# MAIN.net
KiCad netlist of a schematic drawn in Altium Designer
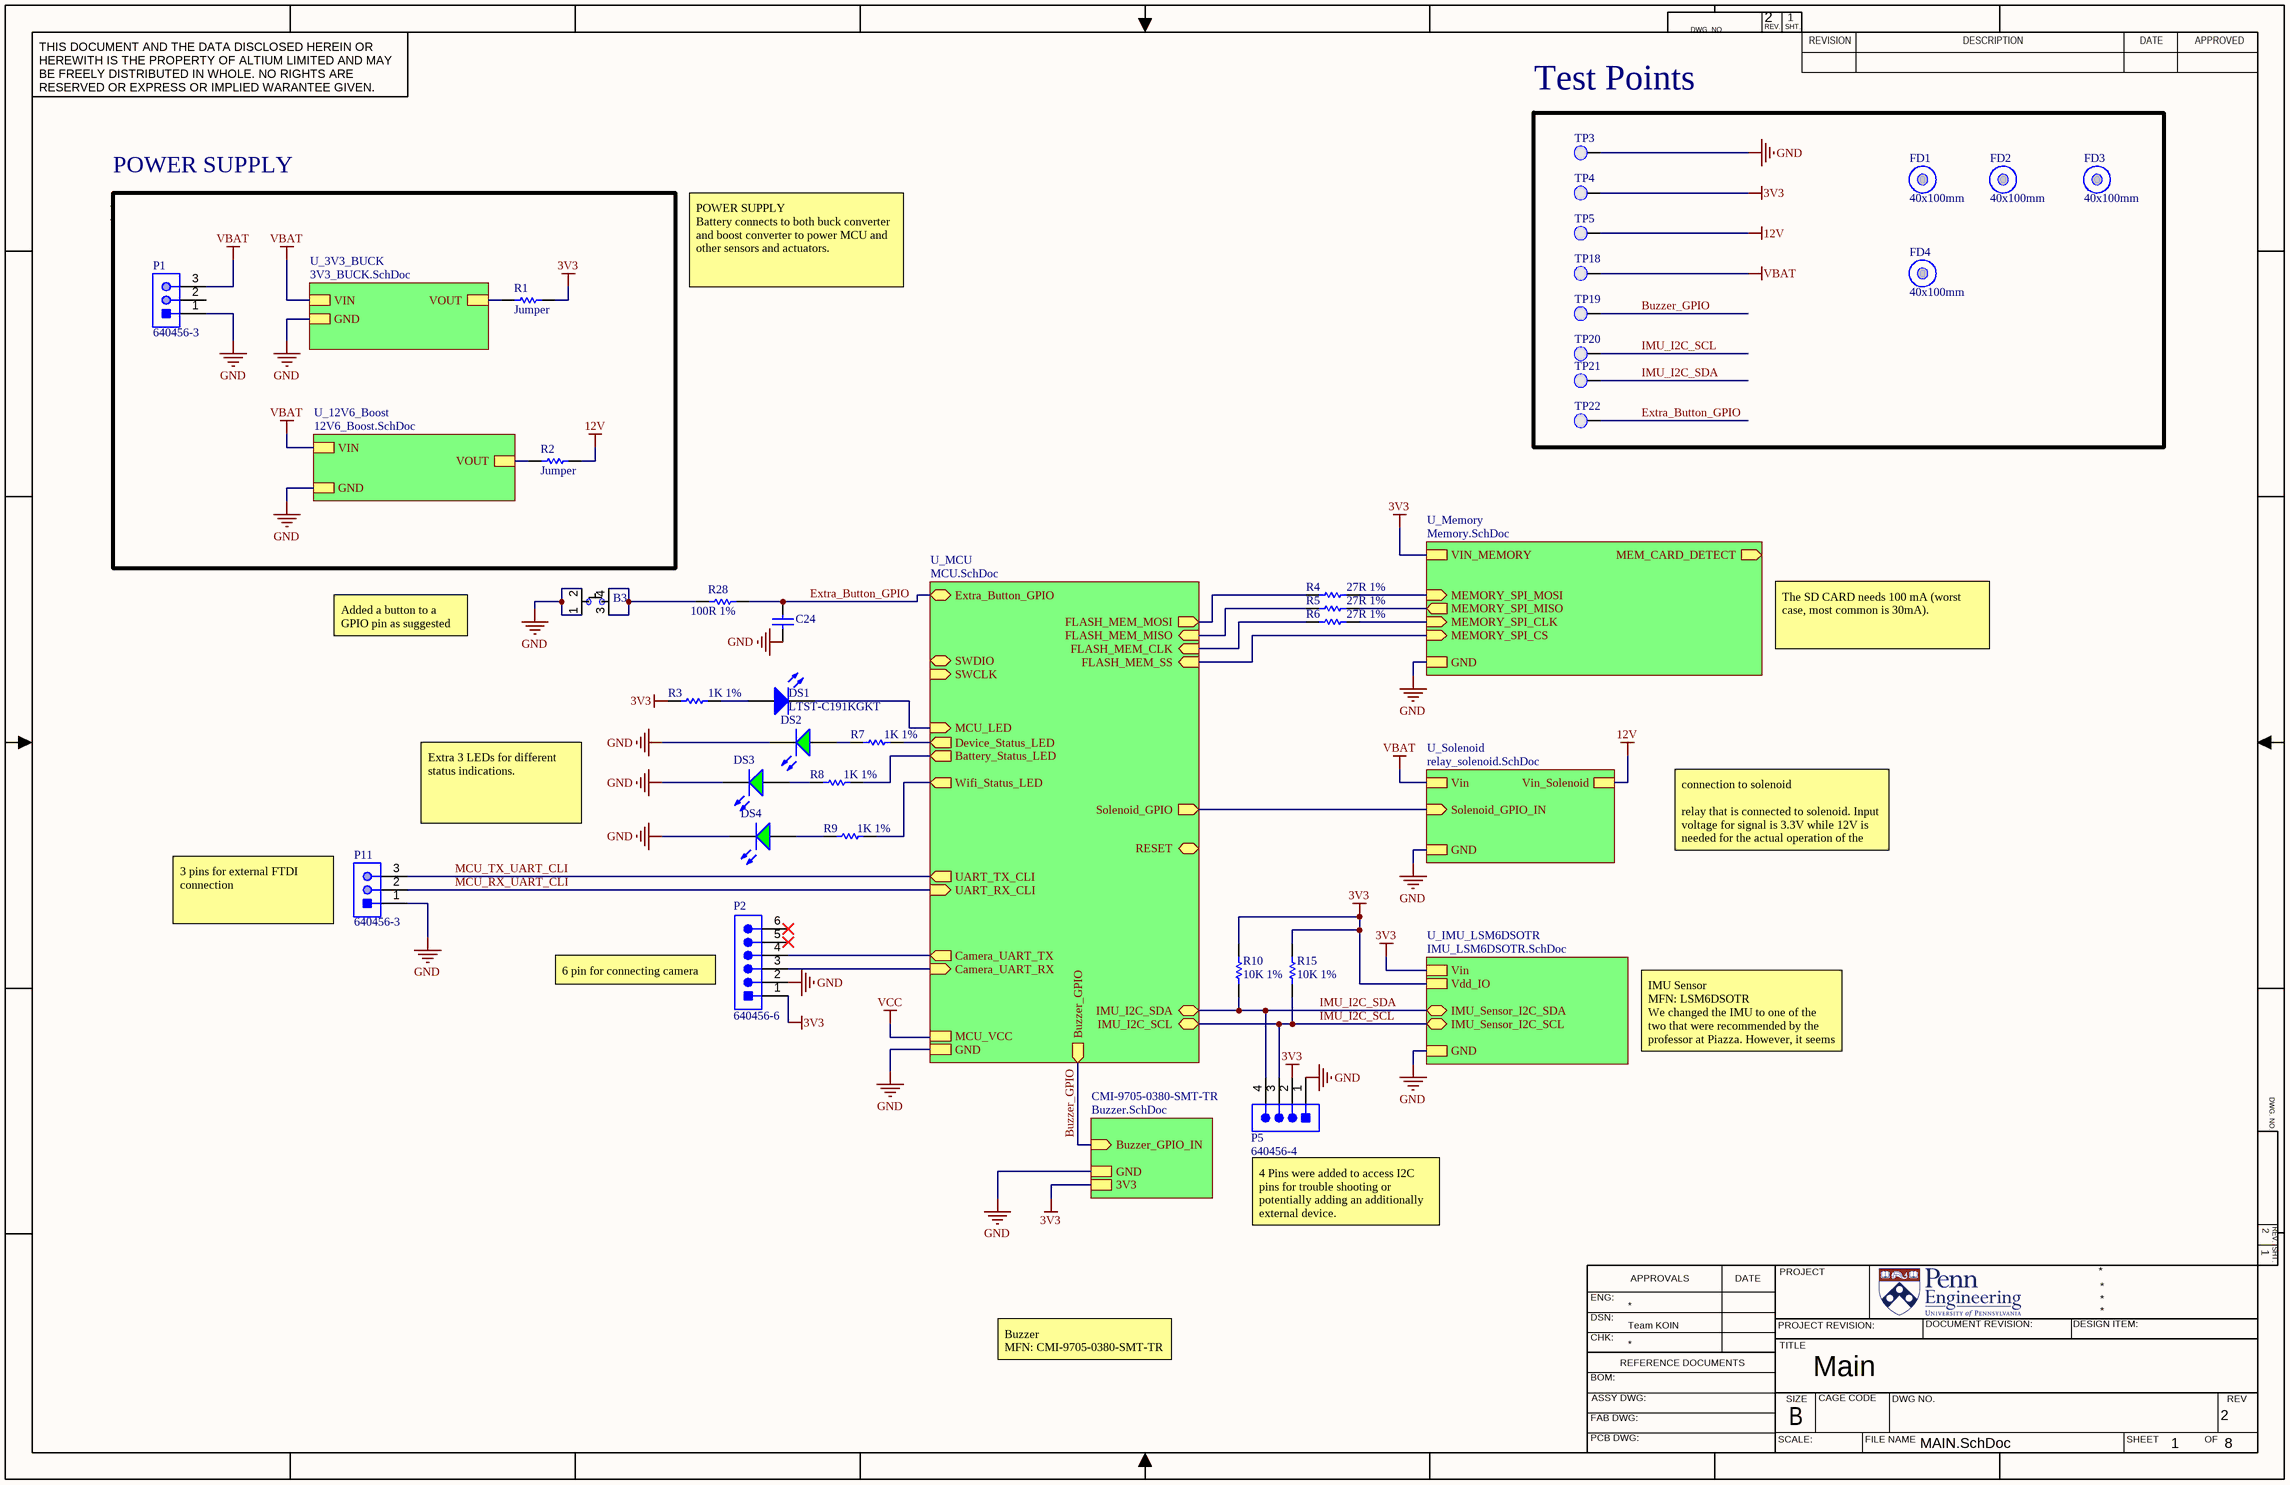
[diagram p0: MAIN.SchDoc]

(export (version "E")
  (design (tool "Eeschema 10.0.6"))
  (components
    (comp (ref "B3")
      (value "PTS810 SJK 250 SMTR LFS")
      (footprint "PTS810 SJK 250 SMTR LFS")
      (description "SWITCH TACTILE SPST-NO 0.05A 16V Tactile Switch SPST-NO Top Actuated Surface Mount")
      (fields
        (field (name "MANUFACTURER") "ITT /  C&K Components")
        (field (name "MANUFACTURER PART NUMBER") "PTS810SJK250SMTRLFS")
      )
      (libsource (lib "Schematics") (part "PTS810 SJK 250 SMTR LFS"))
    )
    (comp (ref "C24")
      (value "CAP 1uF 16V 0603(1608)")
      (footprint "CAPC0603(1608)100_N")
      (description "CAP 1uF 16V ±5% 0603 (1608 Metric) Thickness 1mm SMD")
      (fields (field (name "TOLERANCE") "Â±5%"))
      (libsource (lib "Altium Content Vault") (part "CAP"))
    )
    (comp (ref "DS1")
      (value "LTST-C191KGKT")
      (footprint "LITE-ON-LTST-C191KRKT-2_V")
      (description "Chip LED, Green, 574 nm, 40 pF, -55 to 85 degC, 2-Pin SMD, RoHS, Tape and Reel")
      (fields (field (name "MANUFACTURER") "Lite-On"))
      (libsource (lib "Altium Content Vault") (part "LED-AK-2"))
    )
    (comp (ref "DS2")
      (value "~")
      (footprint "LTST-C170GKT_V")
      (description "LED Uni-Color Green, 100 mW, 120 mA, -55 to 85 degC, 2-Pin SMD, RoHS, Tape and Reel")
      (fields (field (name "MANUFACTURER") "Lite-On"))
      (libsource (lib "Altium Content Vault") (part "LED-GREEN-AK-2"))
    )
    (comp (ref "DS3")
      (value "~")
      (footprint "LTST-C170GKT_V")
      (description "LED Uni-Color Green, 100 mW, 120 mA, -55 to 85 degC, 2-Pin SMD, RoHS, Tape and Reel")
      (fields (field (name "MANUFACTURER") "Lite-On"))
      (libsource (lib "Altium Content Vault") (part "LED-GREEN-AK-2"))
    )
    (comp (ref "DS4")
      (value "~")
      (footprint "LTST-C170GKT_V")
      (description "LED Uni-Color Green, 100 mW, 120 mA, -55 to 85 degC, 2-Pin SMD, RoHS, Tape and Reel")
      (fields (field (name "MANUFACTURER") "Lite-On"))
      (libsource (lib "Altium Content Vault") (part "LED-GREEN-AK-2"))
    )
    (comp (ref "FD1")
      (value "40x100mm")
      (footprint "Fiducial_FT")
      (description "Fiducial 40x100mm")
      (libsource (lib "Components - 01.02.21 - 21.11") (part "CMP-00174-A.4"))
    )
    (comp (ref "FD2")
      (value "40x100mm")
      (footprint "Fiducial_FT")
      (description "Fiducial 40x100mm")
      (libsource (lib "Components - 01.02.21 - 21.11") (part "CMP-00174-A.4"))
    )
    (comp (ref "FD3")
      (value "40x100mm")
      (footprint "Fiducial_FT")
      (description "Fiducial 40x100mm")
      (libsource (lib "Components - 01.02.21 - 21.11") (part "CMP-00174-A.4"))
    )
    (comp (ref "FD4")
      (value "40x100mm")
      (footprint "Fiducial_FT")
      (description "Fiducial 40x100mm")
      (libsource (lib "Components - 01.02.21 - 21.11") (part "CMP-00174-A.4"))
    )
    (comp (ref "P1")
      (value "640456-3")
      (footprint "TECO-640456-3")
      (description "Male Header, Pitch 2.54 mm, 1 x 3 Position, Height 10.03 mm, Tail Length 3.56 mm, -55 to 105 degC")
      (fields (field (name "MANUFACTURER") "TE Connectivity"))
      (libsource (lib "Altium Content Vault") (part "CN-1P-M-R3"))
    )
    (comp (ref "P2")
      (value "640456-6")
      (footprint "TECO-640456-6_V")
      (fields (field (name "MANUFACTURER") "TE Connectivity"))
      (libsource (lib "Altium Content Vault") (part "CN-1P-M-R6"))
    )
    (comp (ref "P5")
      (value "640456-4")
      (footprint "TECO-640456-4")
      (description "Male Header, Pitch 2.54 mm, 1 x 4 Position, Height 10.03 mm, Tail Length 3.56 mm, RoHS, Bulk")
      (fields (field (name "MANUFACTURER") "TE Connectivity"))
      (libsource (lib "Altium Content Vault") (part "CN-1P-M-R4"))
    )
    (comp (ref "P11")
      (value "640456-3")
      (footprint "TECO-640456-3")
      (description "Male Header, Pitch 2.54 mm, 1 x 3 Position, Height 10.03 mm, Tail Length 3.56 mm, -55 to 105 degC")
      (fields (field (name "MANUFACTURER") "TE Connectivity"))
      (libsource (lib "Altium Content Vault") (part "CN-1P-M-R3"))
    )
    (comp (ref "R1")
      (value "Jumper")
      (footprint "RESC0805(2012)_N")
      (description "Jumper 0805 (2012 Metric)")
      (fields (field (name "TOLERANCE") "None"))
      (libsource (lib "Altium Content Vault") (part "RES"))
    )
    (comp (ref "R2")
      (value "Jumper")
      (footprint "RESC0805(2012)_N")
      (description "Jumper 0805 (2012 Metric)")
      (fields (field (name "TOLERANCE") "None"))
      (libsource (lib "Altium Content Vault") (part "RES"))
    )
    (comp (ref "R3")
      (value "1K 1%")
      (footprint "RESC0603(1608)_N")
      (description "1K 0.1W 1% 0603 (1608 Metric)  SMD")
      (fields (field (name "TOLERANCE") "1 %") (field (name "POWER") "0.1 W"))
      (libsource (lib "Altium Content Vault") (part "RES"))
    )
    (comp (ref "R4")
      (value "27R 1%")
      (footprint "RESC0603(1608)_N")
      (description "27R 0.1W 1% 0603 (1608 Metric)  SMD")
      (fields (field (name "TOLERANCE") "1 %") (field (name "POWER") "0.1 W"))
      (libsource (lib "Altium Content Vault") (part "RES"))
    )
    (comp (ref "R5")
      (value "27R 1%")
      (footprint "RESC0603(1608)_N")
      (description "27R 0.1W 1% 0603 (1608 Metric)  SMD")
      (fields (field (name "TOLERANCE") "1 %") (field (name "POWER") "0.1 W"))
      (libsource (lib "Altium Content Vault") (part "RES"))
    )
    (comp (ref "R6")
      (value "27R 1%")
      (footprint "RESC0603(1608)_N")
      (description "27R 0.1W 1% 0603 (1608 Metric)  SMD")
      (fields (field (name "TOLERANCE") "1 %") (field (name "POWER") "0.1 W"))
      (libsource (lib "Altium Content Vault") (part "RES"))
    )
    (comp (ref "R7")
      (value "1K 1%")
      (footprint "RESC0603(1608)_M")
      (description "1K 0.1W 1% 0603 (1608 Metric)  SMD")
      (fields (field (name "TOLERANCE") "1 %") (field (name "POWER") "0.1 W"))
      (libsource (lib "Altium Content Vault") (part "RES"))
    )
    (comp (ref "R8")
      (value "1K 1%")
      (footprint "RESC0603(1608)_M")
      (description "1K 0.1W 1% 0603 (1608 Metric)  SMD")
      (fields (field (name "TOLERANCE") "1 %") (field (name "POWER") "0.1 W"))
      (libsource (lib "Altium Content Vault") (part "RES"))
    )
    (comp (ref "R9")
      (value "1K 1%")
      (footprint "RESC0603(1608)_M")
      (description "1K 0.1W 1% 0603 (1608 Metric)  SMD")
      (fields (field (name "TOLERANCE") "1 %") (field (name "POWER") "0.1 W"))
      (libsource (lib "Altium Content Vault") (part "RES"))
    )
    (comp (ref "R10")
      (value "10K 1%")
      (footprint "RESC0603(1608)_N")
      (description "10K 0.1W 1% 0603 (1608 Metric)  SMD")
      (fields (field (name "POWER") "0.1 W") (field (name "TOLERANCE") "1 %"))
      (libsource (lib "Altium Content Vault") (part "RES"))
    )
    (comp (ref "R15")
      (value "10K 1%")
      (footprint "RESC0603(1608)_N")
      (description "10K 0.1W 1% 0603 (1608 Metric)  SMD")
      (fields (field (name "POWER") "0.1 W") (field (name "TOLERANCE") "1 %"))
      (libsource (lib "Altium Content Vault") (part "RES"))
    )
    (comp (ref "R28")
      (value "100R 1%")
      (footprint "RESC0603(1608)_N")
      (description "100R 0.1W 1% 0603 (1608 Metric)  SMD")
      (fields (field (name "TOLERANCE") "1 %") (field (name "POWER") "0.1 W"))
      (libsource (lib "Altium Content Vault") (part "RES"))
    )
    (comp (ref "TP3")
      (value "0.1\" Pad")
      (footprint "PCBComponent")
      (libsource (lib "Components - 12.02.20 - 18.05") (part "0.1{dblquote} Pad-A.4"))
    )
    (comp (ref "TP4")
      (value "0.1\" Pad")
      (footprint "PCBComponent")
      (libsource (lib "Components - 12.02.20 - 18.05") (part "0.1{dblquote} Pad-A.4"))
    )
    (comp (ref "TP5")
      (value "0.1\" Pad")
      (footprint "PCBComponent")
      (libsource (lib "Components - 12.02.20 - 18.05") (part "0.1{dblquote} Pad-A.4"))
    )
    (comp (ref "TP18")
      (value "0.1\" Pad")
      (footprint "PCBComponent")
      (libsource (lib "Components - 12.02.20 - 18.05") (part "0.1{dblquote} Pad-A.4"))
    )
    (comp (ref "TP19")
      (value "0.1\" Pad")
      (footprint "PCBComponent")
      (libsource (lib "Components - 12.02.20 - 18.05") (part "0.1{dblquote} Pad-A.4"))
    )
    (comp (ref "TP20")
      (value "0.1\" Pad")
      (footprint "PCBComponent")
      (libsource (lib "Components - 12.02.20 - 18.05") (part "0.1{dblquote} Pad-A.4"))
    )
    (comp (ref "TP21")
      (value "0.1\" Pad")
      (footprint "PCBComponent")
      (libsource (lib "Components - 12.02.20 - 18.05") (part "0.1{dblquote} Pad-A.4"))
    )
    (comp (ref "TP22")
      (value "0.1\" Pad")
      (footprint "PCBComponent")
      (libsource (lib "Components - 12.02.20 - 18.05") (part "0.1{dblquote} Pad-A.4"))
    )
  )
  (nets
    (net (code "1") (name "/Battery_Status_LED") (class "Default")
      (node (ref "R8") (pin "1") (pinfunction "1_1") (pintype "passive"))
    )
    (net (code "2") (name "/Buzzer_GPIO") (class "Default")
      (node (ref "TP19") (pin "1") (pinfunction "PAD_1") (pintype "passive"))
    )
    (net (code "3") (name "/Camera_UART_RX") (class "Default")
      (node (ref "P2") (pin "3") (pinfunction "3_3") (pintype "passive"))
    )
    (net (code "4") (name "/Camera_UART_TX") (class "Default")
      (node (ref "P2") (pin "4") (pinfunction "4_4") (pintype "passive"))
    )
    (net (code "5") (name "/Device_Status_LED") (class "Default")
      (node (ref "R7") (pin "1") (pinfunction "1_1") (pintype "passive"))
    )
    (net (code "6") (name "/Extra_Button_GPIO") (class "Default")
      (node (ref "C24") (pin "2") (pinfunction "2_2") (pintype "passive"))
      (node (ref "R28") (pin "2") (pinfunction "2_2") (pintype "passive"))
      (node (ref "TP22") (pin "1") (pinfunction "PAD_1") (pintype "passive"))
    )
    (net (code "7") (name "/FLASH_MEM_CLK") (class "Default")
      (node (ref "R6") (pin "1") (pinfunction "1_1") (pintype "passive"))
    )
    (net (code "8") (name "/FLASH_MEM_MISO") (class "Default")
      (node (ref "R5") (pin "1") (pinfunction "1_1") (pintype "passive"))
    )
    (net (code "9") (name "/FLASH_MEM_MOSI") (class "Default")
      (node (ref "R4") (pin "1") (pinfunction "1_1") (pintype "passive"))
    )
    (net (code "11") (name "/IMU_I2C_SCL") (class "Default")
      (node (ref "P5") (pin "3") (pinfunction "3_3") (pintype "passive"))
      (node (ref "R15") (pin "1") (pinfunction "1_1") (pintype "passive"))
      (node (ref "TP20") (pin "1") (pinfunction "PAD_1") (pintype "passive"))
    )
    (net (code "12") (name "/IMU_I2C_SDA") (class "Default")
      (node (ref "P5") (pin "4") (pinfunction "4_4") (pintype "passive"))
      (node (ref "R10") (pin "1") (pinfunction "1_1") (pintype "passive"))
      (node (ref "TP21") (pin "1") (pinfunction "PAD_1") (pintype "passive"))
    )
    (net (code "13") (name "/MCU_LED") (class "Default")
      (node (ref "DS1") (pin "2") (pinfunction "K_2") (pintype "passive"))
    )
    (net (code "14") (name "/MCU_RX_UART_CLI") (class "Default")
      (node (ref "P11") (pin "2") (pinfunction "2_2") (pintype "passive"))
    )
    (net (code "15") (name "/MCU_TX_UART_CLI") (class "Default")
      (node (ref "P11") (pin "3") (pinfunction "3_3") (pintype "passive"))
    )
    (net (code "17") (name "/MEMORY_SPI_CLK") (class "Default")
      (node (ref "R6") (pin "2") (pinfunction "2_2") (pintype "passive"))
    )
    (net (code "18") (name "/MEMORY_SPI_MISO") (class "Default")
      (node (ref "R5") (pin "2") (pinfunction "2_2") (pintype "passive"))
    )
    (net (code "19") (name "/MEMORY_SPI_MOSI") (class "Default")
      (node (ref "R4") (pin "2") (pinfunction "2_2") (pintype "passive"))
    )
    (net (code "25") (name "/VOUT") (class "Default")
      (node (ref "R2") (pin "1") (pinfunction "1_1") (pintype "passive"))
    )
    (net (code "26") (name "/VOUT_1") (class "Default")
      (node (ref "R1") (pin "1") (pinfunction "1_1") (pintype "passive"))
    )
    (net (code "27") (name "/Wifi_Status_LED") (class "Default")
      (node (ref "R9") (pin "2") (pinfunction "2_2") (pintype "passive"))
    )
    (net (code "28") (name "3V3") (class "Default")
      (node (ref "P2") (pin "1") (pinfunction "1_1") (pintype "passive"))
      (node (ref "P5") (pin "2") (pinfunction "2_2") (pintype "passive"))
      (node (ref "R1") (pin "2") (pinfunction "2_2") (pintype "passive"))
      (node (ref "R10") (pin "2") (pinfunction "2_2") (pintype "passive"))
      (node (ref "R15") (pin "2") (pinfunction "2_2") (pintype "passive"))
      (node (ref "R3") (pin "1") (pinfunction "1_1") (pintype "passive"))
      (node (ref "TP4") (pin "1") (pinfunction "PAD_1") (pintype "passive"))
    )
    (net (code "29") (name "12V") (class "Default")
      (node (ref "R2") (pin "2") (pinfunction "2_2") (pintype "passive"))
      (node (ref "TP5") (pin "1") (pinfunction "PAD_1") (pintype "passive"))
    )
    (net (code "30") (name "GND") (class "Default")
      (node (ref "B3") (pin "1") (pinfunction "1_1") (pintype "power_in"))
      (node (ref "B3") (pin "2") (pinfunction "2_2") (pintype "power_in"))
      (node (ref "C24") (pin "1") (pinfunction "1_1") (pintype "passive"))
      (node (ref "DS2") (pin "2") (pinfunction "K_2") (pintype "passive"))
      (node (ref "DS3") (pin "2") (pinfunction "K_2") (pintype "passive"))
      (node (ref "DS4") (pin "2") (pinfunction "K_2") (pintype "passive"))
      (node (ref "P1") (pin "1") (pinfunction "1_1") (pintype "passive"))
      (node (ref "P11") (pin "1") (pinfunction "1_1") (pintype "passive"))
      (node (ref "P2") (pin "2") (pinfunction "2_2") (pintype "passive"))
      (node (ref "P5") (pin "1") (pinfunction "1_1") (pintype "passive"))
      (node (ref "TP3") (pin "1") (pinfunction "PAD_1") (pintype "passive"))
    )
    (net (code "31") (name "Net-(B3-Pad3)") (class "Default")
      (node (ref "B3") (pin "3") (pinfunction "3_3") (pintype "power_in"))
      (node (ref "B3") (pin "4") (pinfunction "4_4") (pintype "power_in"))
      (node (ref "R28") (pin "1") (pinfunction "1_1") (pintype "passive"))
    )
    (net (code "32") (name "Net-(DS1-A)") (class "Default")
      (node (ref "DS1") (pin "1") (pinfunction "A_1") (pintype "passive"))
      (node (ref "R3") (pin "2") (pinfunction "2_2") (pintype "passive"))
    )
    (net (code "33") (name "Net-(DS2-A)") (class "Default")
      (node (ref "DS2") (pin "1") (pinfunction "A_1") (pintype "passive"))
      (node (ref "R7") (pin "2") (pinfunction "2_2") (pintype "passive"))
    )
    (net (code "34") (name "Net-(DS3-A)") (class "Default")
      (node (ref "DS3") (pin "1") (pinfunction "A_1") (pintype "passive"))
      (node (ref "R8") (pin "2") (pinfunction "2_2") (pintype "passive"))
    )
    (net (code "35") (name "Net-(DS4-A)") (class "Default")
      (node (ref "DS4") (pin "1") (pinfunction "A_1") (pintype "passive"))
      (node (ref "R9") (pin "1") (pinfunction "1_1") (pintype "passive"))
    )
    (net (code "36") (name "VBAT") (class "Default")
      (node (ref "P1") (pin "3") (pinfunction "3_3") (pintype "passive"))
      (node (ref "TP18") (pin "1") (pinfunction "PAD_1") (pintype "passive"))
    )
    (net (code "38") (name "unconnected-(P1-Pad2)") (class "Default")
      (node (ref "P1") (pin "2") (pinfunction "2_2") (pintype "passive"))
    )
    (net (code "39") (name "unconnected-(P2-Pad5)") (class "Default")
      (node (ref "P2") (pin "5") (pinfunction "5_5") (pintype "passive+no_connect"))
    )
    (net (code "40") (name "unconnected-(P2-Pad6)") (class "Default")
      (node (ref "P2") (pin "6") (pinfunction "6_6") (pintype "passive+no_connect"))
    )
  )
)
